# HeatMapNodeV1.net
KiCad netlist of a schematic drawn in Altium Designer
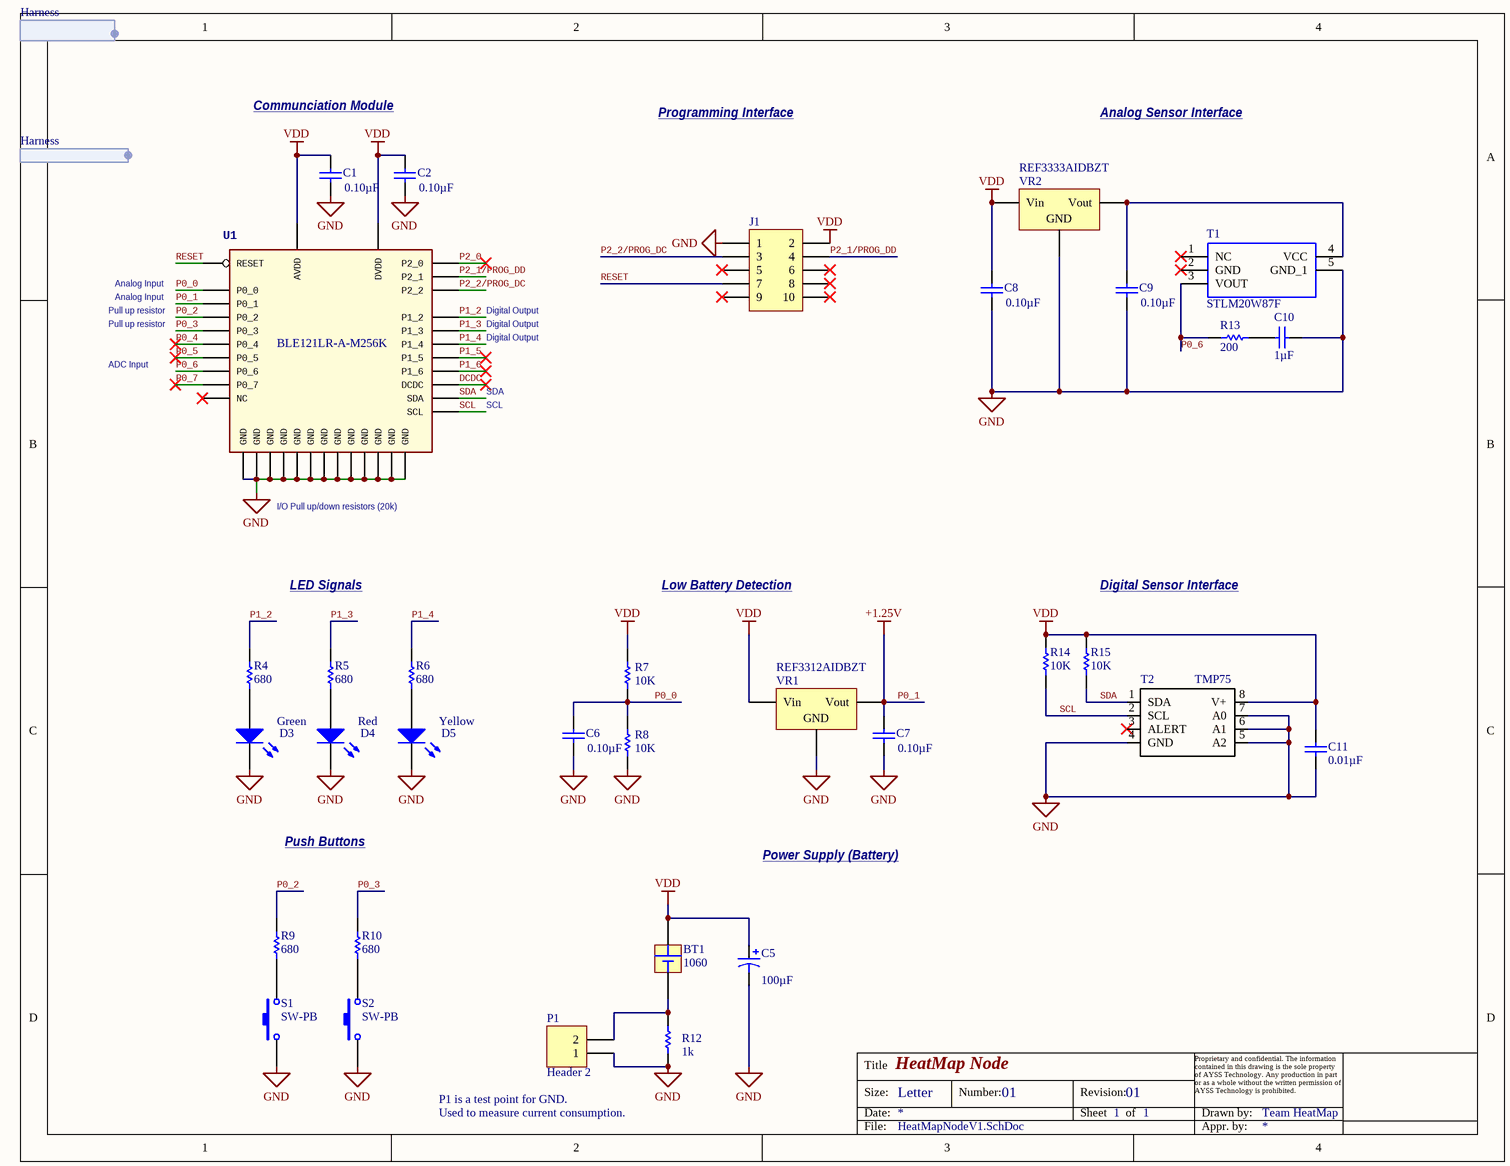
[diagram p0: HeatMapNodeV1.SchDoc]

(export (version "E")
  (design (tool "Eeschema 10.0.6"))
  (components
    (comp (ref "BT1")
      (value "1060")
      (footprint "1060")
      (description "Coin Cell Battery 2032 Holder")
      (fields (field (name "MANUFACTURER") "Keystone Electronics"))
      (libsource (lib "Keystone_1057") (part "Battery"))
    )
    (comp (ref "C1")
      (value "0.10µF")
      (footprint "6-0805_M")
      (description "Capacitor (Semiconductor SIM Model)")
      (fields
        (field (name "MANUFACTURER") "Taiyo Yuden")
        (field (name "MANUFACTURER PART NUMBER") "HMK212B7104KG-T")
        (field (name "PUBLISHER") "Altium Limited")
      )
      (libsource (lib "Miscellaneous Devices") (part "Cap Semi"))
    )
    (comp (ref "C2")
      (value "0.10µF")
      (footprint "6-0805_M")
      (description "Capacitor (Semiconductor SIM Model)")
      (fields
        (field (name "MANUFACTURER") "Taiyo Yuden")
        (field (name "MANUFACTURER PART NUMBER") "HMK212B7104KG-T")
        (field (name "PUBLISHER") "Altium Limited")
      )
      (libsource (lib "Miscellaneous Devices") (part "Cap Semi"))
    )
    (comp (ref "C5")
      (value "100µF")
      (footprint "D")
      (description "Polarized Capacitor (Surface Mount)")
      (fields
        (field (name "MANUFACTURER") "KEMET")
        (field (name "MANUFACTURER PART NUMBER") "T495D107K016ATE125")
        (field (name "PUBLISHER") "Altium Limited")
      )
      (libsource (lib "Miscellaneous Devices") (part "Cap Pol3"))
    )
    (comp (ref "C6")
      (value "0.10µF")
      (footprint "6-0805_M")
      (description "Capacitor (Semiconductor SIM Model)")
      (fields
        (field (name "MANUFACTURER") "Taiyo Yuden")
        (field (name "MANUFACTURER PART NUMBER") "HMK212B7104KG-T")
        (field (name "PUBLISHER") "Altium Limited")
      )
      (libsource (lib "Miscellaneous Devices") (part "Cap Semi"))
    )
    (comp (ref "C7")
      (value "0.10µF")
      (footprint "6-0805_M")
      (description "Capacitor (Semiconductor SIM Model)")
      (fields
        (field (name "MANUFACTURER") "Taiyo Yuden")
        (field (name "MANUFACTURER PART NUMBER") "HMK212B7104KG-T")
        (field (name "PUBLISHER") "Altium Limited")
      )
      (libsource (lib "Miscellaneous Devices") (part "Cap Semi"))
    )
    (comp (ref "C8")
      (value "0.10µF")
      (footprint "6-0805_M")
      (description "Capacitor (Semiconductor SIM Model)")
      (fields
        (field (name "MANUFACTURER") "Taiyo Yuden")
        (field (name "MANUFACTURER PART NUMBER") "HMK212B7104KG-T")
        (field (name "PUBLISHER") "Altium Limited")
      )
      (libsource (lib "Miscellaneous Devices") (part "Cap Semi"))
    )
    (comp (ref "C9")
      (value "0.10µF")
      (footprint "6-0805_M")
      (description "Capacitor (Semiconductor SIM Model)")
      (fields
        (field (name "MANUFACTURER") "Taiyo Yuden")
        (field (name "MANUFACTURER PART NUMBER") "HMK212B7104KG-T")
        (field (name "PUBLISHER") "Altium Limited")
      )
      (libsource (lib "Miscellaneous Devices") (part "Cap Semi"))
    )
    (comp (ref "C10")
      (value "1µF")
      (footprint "6-0805_M")
      (description "Capacitor (Semiconductor SIM Model)")
      (fields
        (field (name "MANUFACTURER") "Taiyo Yuden")
        (field (name "MANUFACTURER PART NUMBER") "HMK212B7104KG-T")
        (field (name "PUBLISHER") "Altium Limited")
      )
      (libsource (lib "Miscellaneous Devices") (part "Cap Semi"))
    )
    (comp (ref "C11")
      (value "0.01µF")
      (footprint "6-0805_M")
      (description "Capacitor (Semiconductor SIM Model)")
      (fields
        (field (name "MANUFACTURER") "Taiyo Yuden")
        (field (name "MANUFACTURER PART NUMBER") "HMK212B7104KG-T")
        (field (name "PUBLISHER") "Altium Limited")
      )
      (libsource (lib "Miscellaneous Devices") (part "Cap Semi"))
    )
    (comp (ref "D3")
      (value "LED2")
      (footprint "2.0X1.25X1.2")
      (description "Typical RED, GREEN, YELLOW, AMBER GaAs LED")
      (fields
        (field (name "MANUFACTURER") "Visual Communications Company - VCC")
        (field (name "MANUFACTURER PART NUMBER") "CMD17-21VGD/TR8")
        (field (name "COLOR") "Green")
      )
      (libsource (lib "Miscellaneous Devices") (part "LED2"))
    )
    (comp (ref "D4")
      (value "LED2")
      (footprint "2.0X1.25X1.2")
      (description "Typical RED, GREEN, YELLOW, AMBER GaAs LED")
      (fields
        (field (name "MANUFACTURER") "Visual Communications Company - VCC")
        (field (name "MANUFACTURER PART NUMBER") "CMD17-21VRD/TR8")
        (field (name "COLOR") "Red")
      )
      (libsource (lib "Miscellaneous Devices") (part "LED2"))
    )
    (comp (ref "D5")
      (value "LED2")
      (footprint "2.0X1.25X1.2")
      (description "Typical RED, GREEN, YELLOW, AMBER GaAs LED")
      (fields
        (field (name "MANUFACTURER") "Visual Communications Company - VCC")
        (field (name "MANUFACTURER PART NUMBER") "CMD17-21VYD/TR8")
        (field (name "COLOR") "Yellow")
      )
      (libsource (lib "Miscellaneous Devices") (part "LED2"))
    )
    (comp (ref "J1")
      (value "Header 5X2")
      (footprint "HDR2X5_SMD_127")
      (description "Header, 5-Pin, Dual row")
      (fields
        (field (name "MANUFACTURER") "Amphenol FCI")
        (field (name "MANUFACTURER PART NUMBER") "20021521-00010T1LF")
        (field (name "PUBLISHER") "Altium Limited")
      )
      (libsource (lib "Miscellaneous Connectors") (part "Header 5X2"))
    )
    (comp (ref "P1")
      (value "Header 2")
      (footprint "HDR1X2")
      (description "Header, 2-Pin")
      (libsource (lib "Miscellaneous Connectors") (part "Header 2"))
    )
    (comp (ref "R4")
      (value "680")
      (footprint "6-0805_M")
      (description "Resistor")
      (fields
        (field (name "MANUFACTURER") "Vishay Dale")
        (field (name "MANUFACTURER PART NUMBER") "CRCW0805680RFKEA")
      )
      (libsource (lib "Miscellaneous Devices") (part "Res1"))
    )
    (comp (ref "R5")
      (value "680")
      (footprint "6-0805_M")
      (description "Resistor")
      (fields
        (field (name "MANUFACTURER") "Vishay Dale")
        (field (name "MANUFACTURER PART NUMBER") "CRCW0805680RFKEA")
      )
      (libsource (lib "Miscellaneous Devices") (part "Res1"))
    )
    (comp (ref "R6")
      (value "680")
      (footprint "6-0805_M")
      (description "Resistor")
      (fields
        (field (name "MANUFACTURER") "Vishay Dale")
        (field (name "MANUFACTURER PART NUMBER") "CRCW0805680RFKEA")
      )
      (libsource (lib "Miscellaneous Devices") (part "Res1"))
    )
    (comp (ref "R7")
      (value "10K")
      (footprint "6-0805_M")
      (description "Resistor")
      (fields
        (field (name "MANUFACTURER") "Vishay Dale")
        (field (name "MANUFACTURER PART NUMBER") "CRCW080510K0FKEA")
      )
      (libsource (lib "Miscellaneous Devices") (part "Res1"))
    )
    (comp (ref "R8")
      (value "10K")
      (footprint "6-0805_M")
      (description "Resistor")
      (fields
        (field (name "MANUFACTURER") "Vishay Dale")
        (field (name "MANUFACTURER PART NUMBER") "CRCW080510K0FKEA")
      )
      (libsource (lib "Miscellaneous Devices") (part "Res1"))
    )
    (comp (ref "R9")
      (value "680")
      (footprint "6-0805_M")
      (description "Resistor")
      (fields
        (field (name "MANUFACTURER") "Vishay Dale")
        (field (name "MANUFACTURER PART NUMBER") "CRCW0805680RFKEA")
      )
      (libsource (lib "Miscellaneous Devices") (part "Res1"))
    )
    (comp (ref "R10")
      (value "680")
      (footprint "6-0805_M")
      (description "Resistor")
      (fields
        (field (name "MANUFACTURER") "Vishay Dale")
        (field (name "MANUFACTURER PART NUMBER") "CRCW0805680RFKEA")
      )
      (libsource (lib "Miscellaneous Devices") (part "Res1"))
    )
    (comp (ref "R12")
      (value "1k")
      (footprint "6-0805_M")
      (description "Resistor")
      (fields
        (field (name "MANUFACTURER") "Vishay Dale")
        (field (name "MANUFACTURER PART NUMBER") "CRCW08050000Z0EA")
      )
      (libsource (lib "Miscellaneous Devices") (part "Res1"))
    )
    (comp (ref "R13")
      (value "200")
      (footprint "6-0805_M")
      (description "Resistor")
      (fields
        (field (name "MANUFACTURER") "Vishay Dale")
        (field (name "MANUFACTURER PART NUMBER") "CRCW0805680RFKEA")
      )
      (libsource (lib "Miscellaneous Devices") (part "Res1"))
    )
    (comp (ref "R14")
      (value "10K")
      (footprint "6-0805_M")
      (description "Resistor")
      (fields
        (field (name "MANUFACTURER") "Vishay Dale")
        (field (name "MANUFACTURER PART NUMBER") "CRCW0805680RFKEA")
      )
      (libsource (lib "Miscellaneous Devices") (part "Res1"))
    )
    (comp (ref "R15")
      (value "10K")
      (footprint "6-0805_M")
      (description "Resistor")
      (fields
        (field (name "MANUFACTURER") "Vishay Dale")
        (field (name "MANUFACTURER PART NUMBER") "CRCW0805680RFKEA")
      )
      (libsource (lib "Miscellaneous Devices") (part "Res1"))
    )
    (comp (ref "S1")
      (value "SW-PB")
      (footprint "SA")
      (description "Switch")
      (fields
        (field (name "MANUFACTURER") "C&K")
        (field (name "MANUFACTURER PART NUMBER") "EP11FPD1SAPE(T&R)")
      )
      (libsource (lib "Miscellaneous Devices") (part "SW-PB"))
    )
    (comp (ref "S2")
      (value "SW-PB")
      (footprint "SA")
      (description "Switch")
      (fields
        (field (name "MANUFACTURER") "C&K")
        (field (name "MANUFACTURER PART NUMBER") "EP11FPD1SAPE(T&R)")
      )
      (libsource (lib "Miscellaneous Devices") (part "SW-PB"))
    )
    (comp (ref "T1")
      (value "STLM20W87F")
      (footprint "SOT65P210X110-5N")
      (description "STLM20W87F, Temperature Sensor 1.5C 2.4 to 5.5V 5-Pin SOT-323")
      (fields (field (name "RS PART NUMBER") "1685835"))
      (libsource (lib "STLM20W87F") (part "STLM20W87F"))
    )
    (comp (ref "T2")
      (value "TMP75")
      (footprint "MSOP8")
      (fields (field (name "MF") "Texas Instruments"))
      (libsource (lib "TMP75") (part "TMP75"))
    )
    (comp (ref "U1")
      (value "BLE121LR module")
      (footprint "BLE121LR")
      (description "Bluetooth Low Energy (BLE) module")
      (fields
        (field (name "MANUFACTURER") "Silicon Labs")
        (field (name "MANUFACTURER PART NUMBER") "BLE121LR-A-M256K")
      )
      (libsource (lib "BLE121LR") (part "BLE121LR"))
    )
    (comp (ref "VR1")
      (value "Volt Reg")
      (footprint "SOT23_M")
      (description "Voltage Regulator")
      (fields
        (field (name "MANUFACTURER") "Texas Instruments")
        (field (name "MANUFACTURER PART NUMBER") "REF3312AIDBZT")
        (field (name "TOLERANCE") "±0.15%")
      )
      (libsource (lib "Miscellaneous Devices") (part "Volt Reg"))
    )
    (comp (ref "VR2")
      (value "Volt Reg")
      (footprint "SOT23_M")
      (description "Voltage Regulator")
      (fields
        (field (name "MANUFACTURER") "Texas Instruments")
        (field (name "MANUFACTURER PART NUMBER") "REF3333AIDBZT")
        (field (name "TOLERANCE") "±0.15%")
      )
      (libsource (lib "Miscellaneous Devices") (part "Volt Reg"))
    )
  )
  (nets
    (net (code "1") (name "+1.25V") (class "Default")
      (node (ref "C7") (pin "2") (pinfunction "2_2") (pintype "passive"))
      (node (ref "U1") (pin "5") (pinfunction "P0_1_5") (pintype "passive"))
      (node (ref "VR1") (pin "3") (pinfunction "Vout_3") (pintype "passive"))
    )
    (net (code "2") (name "/DCDC") (class "Default")
      (node (ref "U1") (pin "18") (pinfunction "DCDC_18") (pintype "passive+no_connect"))
    )
    (net (code "3") (name "/P0_0") (class "Default")
      (node (ref "C6") (pin "2") (pinfunction "2_2") (pintype "passive"))
      (node (ref "R7") (pin "1") (pinfunction "1_1") (pintype "passive"))
      (node (ref "R8") (pin "2") (pinfunction "2_2") (pintype "passive"))
      (node (ref "U1") (pin "6") (pinfunction "P0_0_6") (pintype "passive"))
    )
    (net (code "4") (name "/P0_2") (class "Default")
      (node (ref "R9") (pin "1") (pinfunction "1_1") (pintype "passive"))
      (node (ref "U1") (pin "4") (pinfunction "P0_2_4") (pintype "passive"))
    )
    (net (code "5") (name "/P0_3") (class "Default")
      (node (ref "R10") (pin "1") (pinfunction "1_1") (pintype "passive"))
      (node (ref "U1") (pin "8") (pinfunction "P0_3_8") (pintype "passive"))
    )
    (net (code "6") (name "/P0_4") (class "Default")
      (node (ref "U1") (pin "9") (pinfunction "P0_4_9") (pintype "passive+no_connect"))
    )
    (net (code "7") (name "/P0_5") (class "Default")
      (node (ref "U1") (pin "10") (pinfunction "P0_5_10") (pintype "passive+no_connect"))
    )
    (net (code "8") (name "/P0_6") (class "Default")
      (node (ref "R13") (pin "1") (pinfunction "1_1") (pintype "passive"))
      (node (ref "T1") (pin "3") (pinfunction "VOUT_3") (pintype "passive"))
      (node (ref "U1") (pin "11") (pinfunction "P0_6_11") (pintype "passive"))
    )
    (net (code "9") (name "/P0_7") (class "Default")
      (node (ref "U1") (pin "12") (pinfunction "P0_7_12") (pintype "passive+no_connect"))
    )
    (net (code "10") (name "/P1_2") (class "Default")
      (node (ref "R4") (pin "1") (pinfunction "1_1") (pintype "passive"))
      (node (ref "U1") (pin "30") (pinfunction "P1_2_30") (pintype "passive"))
    )
    (net (code "11") (name "/P1_3") (class "Default")
      (node (ref "R5") (pin "1") (pinfunction "1_1") (pintype "passive"))
      (node (ref "U1") (pin "29") (pinfunction "P1_3_29") (pintype "passive"))
    )
    (net (code "12") (name "/P1_4") (class "Default")
      (node (ref "R6") (pin "1") (pinfunction "1_1") (pintype "passive"))
      (node (ref "U1") (pin "28") (pinfunction "P1_4_28") (pintype "passive"))
    )
    (net (code "13") (name "/P1_5") (class "Default")
      (node (ref "U1") (pin "27") (pinfunction "P1_5_27") (pintype "passive+no_connect"))
    )
    (net (code "14") (name "/P1_6") (class "Default")
      (node (ref "U1") (pin "17") (pinfunction "P1_6_17") (pintype "passive+no_connect"))
    )
    (net (code "15") (name "/P2_0") (class "Default")
      (node (ref "U1") (pin "19") (pinfunction "P2_0_19") (pintype "passive+no_connect"))
    )
    (net (code "16") (name "/P2_1{slash}PROG_DD") (class "Default")
      (node (ref "J1") (pin "4") (pinfunction "4_4") (pintype "passive"))
      (node (ref "U1") (pin "20") (pinfunction "P2_1_20") (pintype "passive"))
    )
    (net (code "17") (name "/P2_2{slash}PROG_DC") (class "Default")
      (node (ref "J1") (pin "3") (pinfunction "3_3") (pintype "passive"))
      (node (ref "U1") (pin "21") (pinfunction "P2_2_21") (pintype "passive"))
    )
    (net (code "18") (name "/RESET") (class "Default")
      (node (ref "J1") (pin "7") (pinfunction "7_7") (pintype "passive"))
      (node (ref "U1") (pin "7") (pinfunction "RESET_7") (pintype "passive"))
    )
    (net (code "19") (name "/SCL") (class "Default")
      (node (ref "R14") (pin "2") (pinfunction "2_2") (pintype "passive"))
      (node (ref "T2") (pin "2") (pinfunction "SCL_2") (pintype "bidirectional"))
      (node (ref "U1") (pin "24") (pinfunction "SCL_24") (pintype "passive"))
    )
    (net (code "20") (name "/SDA") (class "Default")
      (node (ref "R15") (pin "2") (pinfunction "2_2") (pintype "passive"))
      (node (ref "T2") (pin "1") (pinfunction "SDA_1") (pintype "bidirectional"))
      (node (ref "U1") (pin "25") (pinfunction "SDA_25") (pintype "passive"))
    )
    (net (code "21") (name "GND") (class "Default")
      (node (ref "C1") (pin "1") (pinfunction "1_1") (pintype "passive"))
      (node (ref "C10") (pin "1") (pinfunction "1_1") (pintype "passive"))
      (node (ref "C11") (pin "1") (pinfunction "1_1") (pintype "passive"))
      (node (ref "C2") (pin "1") (pinfunction "1_1") (pintype "passive"))
      (node (ref "C5") (pin "2") (pinfunction "2_2") (pintype "passive"))
      (node (ref "C6") (pin "1") (pinfunction "1_1") (pintype "passive"))
      (node (ref "C7") (pin "1") (pinfunction "1_1") (pintype "passive"))
      (node (ref "C8") (pin "1") (pinfunction "1_1") (pintype "passive"))
      (node (ref "C9") (pin "1") (pinfunction "1_1") (pintype "passive"))
      (node (ref "D3") (pin "2") (pinfunction "K_2") (pintype "passive"))
      (node (ref "D4") (pin "2") (pinfunction "K_2") (pintype "passive"))
      (node (ref "D5") (pin "2") (pinfunction "K_2") (pintype "passive"))
      (node (ref "J1") (pin "1") (pinfunction "1_1") (pintype "passive"))
      (node (ref "P1") (pin "1") (pinfunction "1_1") (pintype "passive"))
      (node (ref "R12") (pin "2") (pinfunction "2_2") (pintype "passive"))
      (node (ref "R8") (pin "1") (pinfunction "1_1") (pintype "passive"))
      (node (ref "S1") (pin "1") (pinfunction "1_1") (pintype "passive"))
      (node (ref "S2") (pin "1") (pinfunction "1_1") (pintype "passive"))
      (node (ref "T1") (pin "5") (pinfunction "GND_1_5") (pintype "passive"))
      (node (ref "T2") (pin "4") (pinfunction "GND_4") (pintype "bidirectional"))
      (node (ref "T2") (pin "5") (pinfunction "A2_5") (pintype "bidirectional"))
      (node (ref "T2") (pin "6") (pinfunction "A1_6") (pintype "bidirectional"))
      (node (ref "T2") (pin "7") (pinfunction "A0_7") (pintype "bidirectional"))
      (node (ref "U1") (pin "1") (pinfunction "GND_1") (pintype "power_in"))
      (node (ref "U1") (pin "14") (pinfunction "GND_14") (pintype "power_in"))
      (node (ref "U1") (pin "15") (pinfunction "GND_15") (pintype "power_in"))
      (node (ref "U1") (pin "16") (pinfunction "GND_16") (pintype "power_in"))
      (node (ref "U1") (pin "2") (pinfunction "GND_2") (pintype "power_in"))
      (node (ref "U1") (pin "22") (pinfunction "GND_22") (pintype "power_in"))
      (node (ref "U1") (pin "3") (pinfunction "GND_3") (pintype "power_in"))
      (node (ref "U1") (pin "31") (pinfunction "GND_31") (pintype "power_in"))
      (node (ref "U1") (pin "32") (pinfunction "GND_32") (pintype "power_in"))
      (node (ref "U1") (pin "33") (pinfunction "GND_33") (pintype "power_in"))
      (node (ref "U1") (pin "34") (pinfunction "GND_34") (pintype "power_in"))
      (node (ref "U1") (pin "35") (pinfunction "GND_35") (pintype "power_in"))
      (node (ref "U1") (pin "36") (pinfunction "GND_36") (pintype "power_in"))
      (node (ref "VR1") (pin "2") (pinfunction "GND_2") (pintype "passive"))
      (node (ref "VR2") (pin "2") (pinfunction "GND_2") (pintype "passive"))
    )
    (net (code "22") (name "Net-(BT1--)") (class "Default")
      (node (ref "BT1") (pin "1") (pinfunction "-_1") (pintype "passive"))
      (node (ref "P1") (pin "2") (pinfunction "2_2") (pintype "passive"))
      (node (ref "R12") (pin "1") (pinfunction "1_1") (pintype "passive"))
    )
    (net (code "23") (name "Net-(C10-Pad2)") (class "Default")
      (node (ref "C10") (pin "2") (pinfunction "2_2") (pintype "passive"))
      (node (ref "R13") (pin "2") (pinfunction "2_2") (pintype "passive"))
    )
    (net (code "24") (name "Net-(D3-A)") (class "Default")
      (node (ref "D3") (pin "1") (pinfunction "A_1") (pintype "passive"))
      (node (ref "R4") (pin "2") (pinfunction "2_2") (pintype "passive"))
    )
    (net (code "25") (name "Net-(D4-A)") (class "Default")
      (node (ref "D4") (pin "1") (pinfunction "A_1") (pintype "passive"))
      (node (ref "R5") (pin "2") (pinfunction "2_2") (pintype "passive"))
    )
    (net (code "26") (name "Net-(D5-A)") (class "Default")
      (node (ref "D5") (pin "1") (pinfunction "A_1") (pintype "passive"))
      (node (ref "R6") (pin "2") (pinfunction "2_2") (pintype "passive"))
    )
    (net (code "27") (name "Net-(R9-Pad2)") (class "Default")
      (node (ref "R9") (pin "2") (pinfunction "2_2") (pintype "passive"))
      (node (ref "S1") (pin "2") (pinfunction "2_2") (pintype "passive"))
    )
    (net (code "28") (name "Net-(R10-Pad2)") (class "Default")
      (node (ref "R10") (pin "2") (pinfunction "2_2") (pintype "passive"))
      (node (ref "S2") (pin "2") (pinfunction "2_2") (pintype "passive"))
    )
    (net (code "29") (name "Net-(T1-VCC)") (class "Default")
      (node (ref "C9") (pin "2") (pinfunction "2_2") (pintype "passive"))
      (node (ref "T1") (pin "4") (pinfunction "VCC_4") (pintype "power_in"))
      (node (ref "VR2") (pin "3") (pinfunction "Vout_3") (pintype "passive"))
    )
    (net (code "30") (name "VDD") (class "Default")
      (node (ref "BT1") (pin "2") (pinfunction "+_2") (pintype "passive"))
      (node (ref "C1") (pin "2") (pinfunction "2_2") (pintype "passive"))
      (node (ref "C11") (pin "2") (pinfunction "2_2") (pintype "passive"))
      (node (ref "C2") (pin "2") (pinfunction "2_2") (pintype "passive"))
      (node (ref "C5") (pin "1") (pinfunction "1_1") (pintype "passive"))
      (node (ref "C8") (pin "2") (pinfunction "2_2") (pintype "passive"))
      (node (ref "J1") (pin "2") (pinfunction "2_2") (pintype "passive"))
      (node (ref "R14") (pin "1") (pinfunction "1_1") (pintype "passive"))
      (node (ref "R15") (pin "1") (pinfunction "1_1") (pintype "passive"))
      (node (ref "R7") (pin "2") (pinfunction "2_2") (pintype "passive"))
      (node (ref "T2") (pin "8") (pinfunction "V+_8") (pintype "bidirectional"))
      (node (ref "U1") (pin "13") (pinfunction "AVDD_13") (pintype "power_in"))
      (node (ref "U1") (pin "23") (pinfunction "DVDD_23") (pintype "power_in"))
      (node (ref "VR1") (pin "1") (pinfunction "Vin_1") (pintype "passive"))
      (node (ref "VR2") (pin "1") (pinfunction "Vin_1") (pintype "passive"))
    )
    (net (code "31") (name "unconnected-(J1-Pad5)") (class "Default")
      (node (ref "J1") (pin "5") (pinfunction "5_5") (pintype "passive+no_connect"))
    )
    (net (code "32") (name "unconnected-(J1-Pad6)") (class "Default")
      (node (ref "J1") (pin "6") (pinfunction "6_6") (pintype "passive+no_connect"))
    )
    (net (code "33") (name "unconnected-(J1-Pad8)") (class "Default")
      (node (ref "J1") (pin "8") (pinfunction "8_8") (pintype "passive+no_connect"))
    )
    (net (code "34") (name "unconnected-(J1-Pad9)") (class "Default")
      (node (ref "J1") (pin "9") (pinfunction "9_9") (pintype "passive+no_connect"))
    )
    (net (code "35") (name "unconnected-(J1-Pad10)") (class "Default")
      (node (ref "J1") (pin "10") (pinfunction "10_10") (pintype "passive+no_connect"))
    )
    (net (code "36") (name "unconnected-(T1-GND-Pad2)") (class "Default")
      (node (ref "T1") (pin "2") (pinfunction "GND_2") (pintype "passive+no_connect"))
    )
    (net (code "37") (name "unconnected-(T1-NC-Pad1)") (class "Default")
      (node (ref "T1") (pin "1") (pinfunction "NC_1") (pintype "passive+no_connect"))
    )
    (net (code "38") (name "unconnected-(T2-ALERT-Pad3)") (class "Default")
      (node (ref "T2") (pin "3") (pinfunction "ALERT_3") (pintype "bidirectional+no_connect"))
    )
    (net (code "39") (name "unconnected-(U1-NC-Pad26)") (class "Default")
      (node (ref "U1") (pin "26") (pinfunction "NC_26") (pintype "passive+no_connect"))
    )
  )
)
